# NanoRemotev2.net
KiCad netlist of a schematic drawn in EAGLE
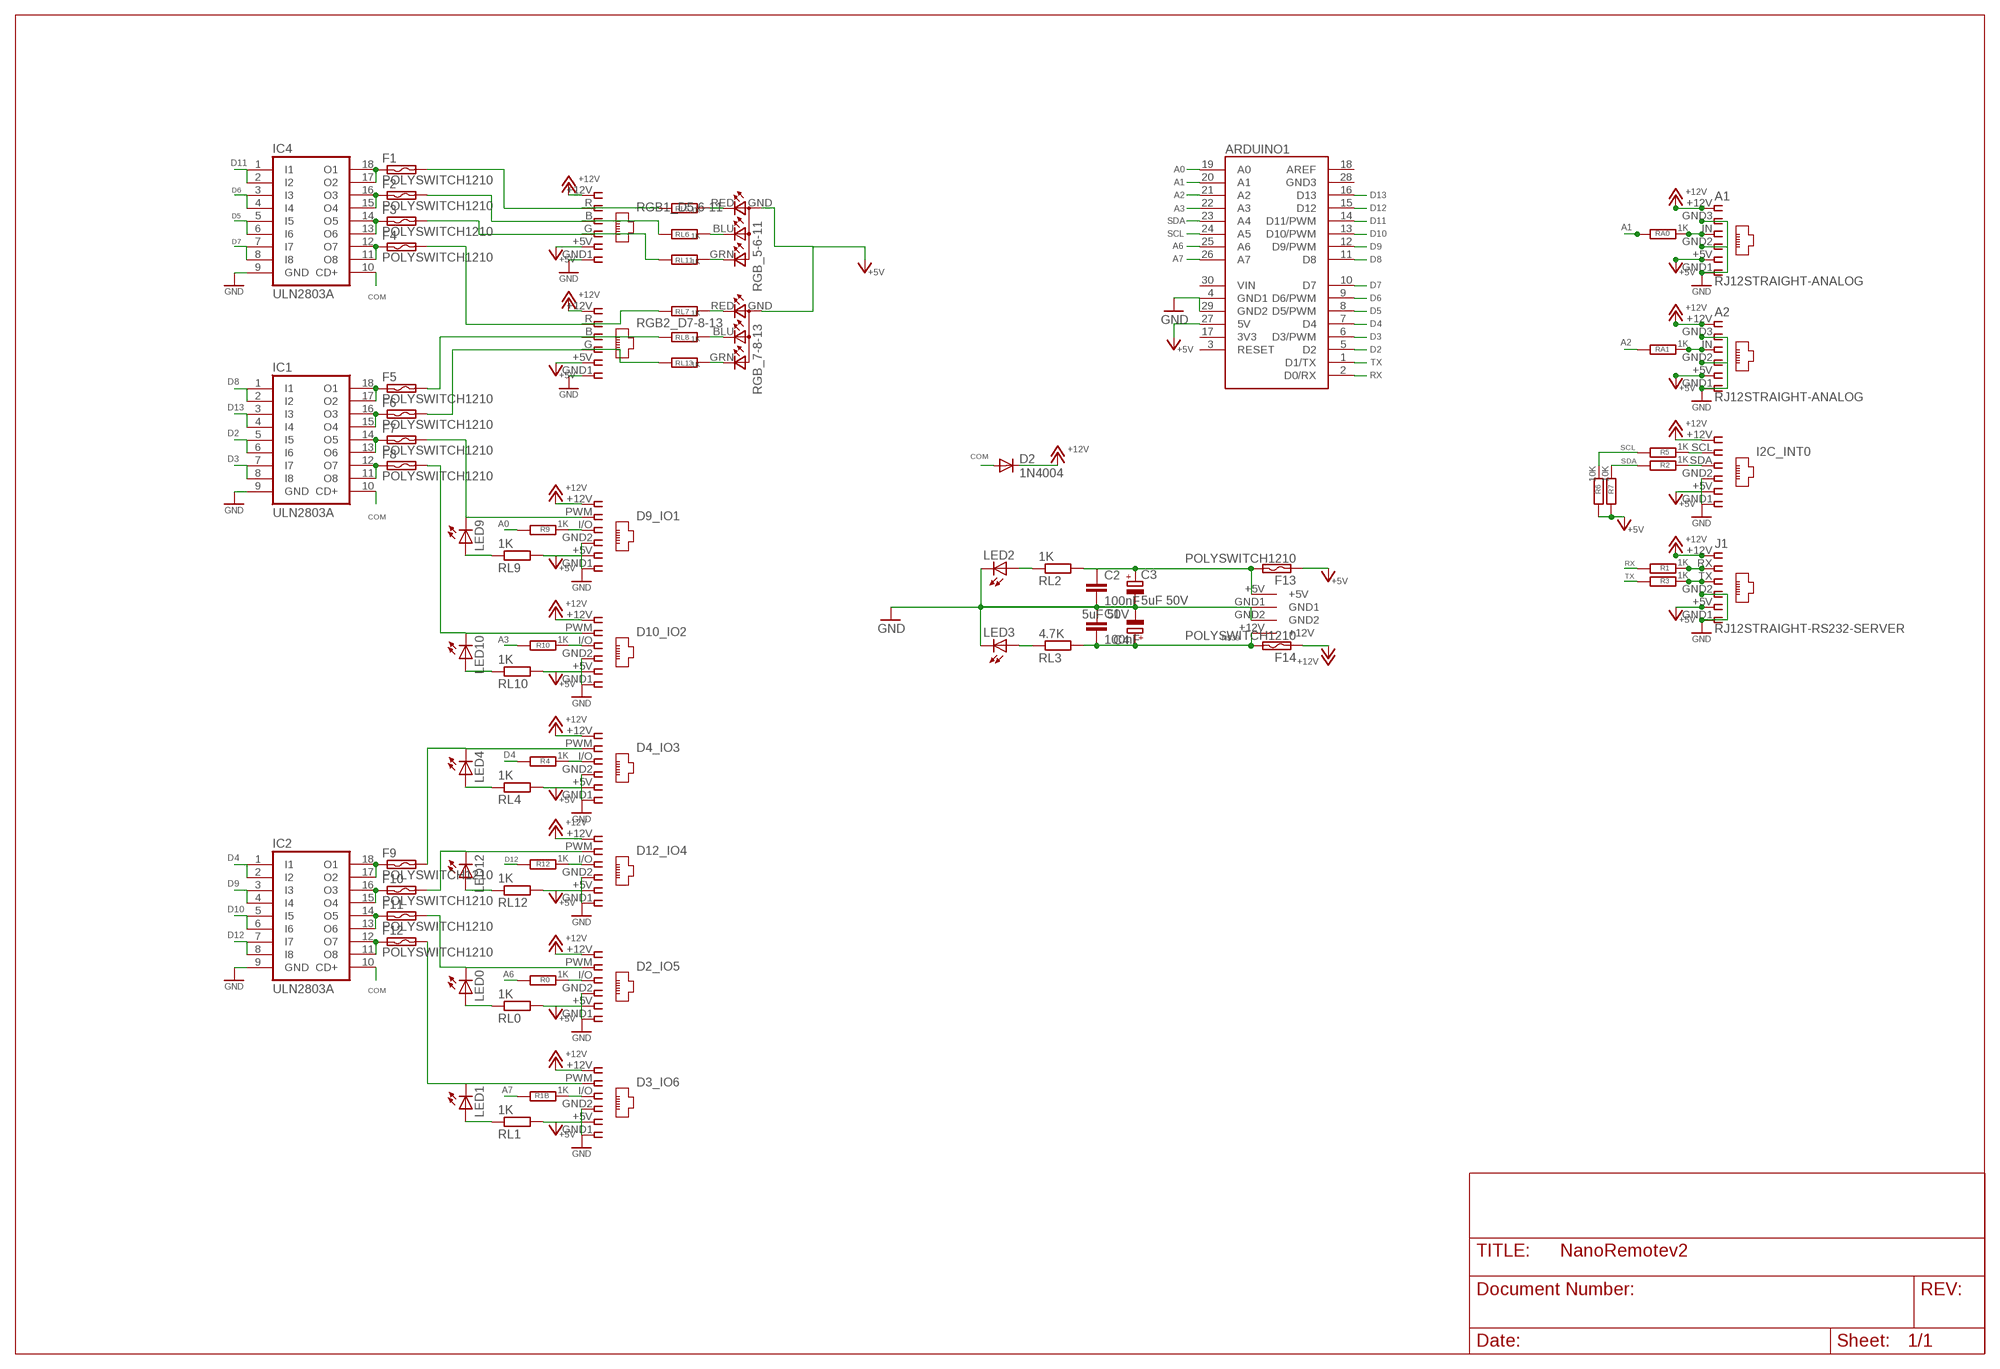
[diagram p0: schematic, sheet 1]

(export (version "E")
  (design (tool "Eeschema 10.0.6"))
  (components
    (comp (ref "A1")
      (value "RJ12STRAIGHT-ANALOG")
      (footprint "eagle-import:RJ12-STRAIGHT-ANALOG")
      (libsource (lib "eagle-import") (part "RJ12STRAIGHT-ANALOG"))
    )
    (comp (ref "A2")
      (value "RJ12STRAIGHT-ANALOG")
      (footprint "eagle-import:RJ12-STRAIGHT-ANALOG")
      (libsource (lib "eagle-import") (part "RJ12STRAIGHT-ANALOG"))
    )
    (comp (ref "ARDUINO1")
      (value "ARDUINO_NANO")
      (footprint "eagle-import:ARDUINO_NANO")
      (libsource (lib "eagle-import") (part "ARDUINO_NANO"))
    )
    (comp (ref "C1")
      (value "100nF")
      (footprint "eagle-import:C1206")
      (libsource (lib "eagle-import") (part "C-EUC1206"))
    )
    (comp (ref "C2")
      (value "100nF")
      (footprint "eagle-import:C1206")
      (libsource (lib "eagle-import") (part "C-EUC1206"))
    )
    (comp (ref "C3")
      (value "5uF 50V")
      (footprint "eagle-import:E3,5-8")
      (libsource (lib "eagle-import") (part "CPOL-EUE3.5-8"))
    )
    (comp (ref "C4")
      (value "5uF 50V")
      (footprint "eagle-import:E3,5-8")
      (libsource (lib "eagle-import") (part "CPOL-EUE3.5-8"))
    )
    (comp (ref "D2")
      (value "1N4004")
      (footprint "eagle-import:DO41-10")
      (libsource (lib "eagle-import") (part "1N4004"))
    )
    (comp (ref "D2_IO5")
      (value "IO5")
      (footprint "eagle-import:RJ12-STRAIGHT")
      (libsource (lib "eagle-import") (part "RJ12STRAIGHT"))
    )
    (comp (ref "D3_IO6")
      (value "IO6")
      (footprint "eagle-import:RJ12-STRAIGHT")
      (libsource (lib "eagle-import") (part "RJ12STRAIGHT"))
    )
    (comp (ref "D4_IO3")
      (value "IO3")
      (footprint "eagle-import:RJ12-STRAIGHT")
      (libsource (lib "eagle-import") (part "RJ12STRAIGHT"))
    )
    (comp (ref "D9_IO1")
      (value "IO1")
      (footprint "eagle-import:RJ12-STRAIGHT")
      (libsource (lib "eagle-import") (part "RJ12STRAIGHT"))
    )
    (comp (ref "D10_IO2")
      (value "IO2")
      (footprint "eagle-import:RJ12-STRAIGHT")
      (libsource (lib "eagle-import") (part "RJ12STRAIGHT"))
    )
    (comp (ref "D12_IO4")
      (value "IO4")
      (footprint "eagle-import:RJ12-STRAIGHT")
      (libsource (lib "eagle-import") (part "RJ12STRAIGHT"))
    )
    (comp (ref "F1")
      (value "POLYSWITCH1210")
      (footprint "eagle-import:C1210")
      (libsource (lib "eagle-import") (part "POLYSWITCH1210"))
    )
    (comp (ref "F2")
      (value "POLYSWITCH1210")
      (footprint "eagle-import:C1210")
      (libsource (lib "eagle-import") (part "POLYSWITCH1210"))
    )
    (comp (ref "F3")
      (value "POLYSWITCH1210")
      (footprint "eagle-import:C1210")
      (libsource (lib "eagle-import") (part "POLYSWITCH1210"))
    )
    (comp (ref "F4")
      (value "POLYSWITCH1210")
      (footprint "eagle-import:C1210")
      (libsource (lib "eagle-import") (part "POLYSWITCH1210"))
    )
    (comp (ref "F5")
      (value "POLYSWITCH1210")
      (footprint "eagle-import:C1210")
      (libsource (lib "eagle-import") (part "POLYSWITCH1210"))
    )
    (comp (ref "F6")
      (value "POLYSWITCH1210")
      (footprint "eagle-import:C1210")
      (libsource (lib "eagle-import") (part "POLYSWITCH1210"))
    )
    (comp (ref "F7")
      (value "POLYSWITCH1210")
      (footprint "eagle-import:C1210")
      (libsource (lib "eagle-import") (part "POLYSWITCH1210"))
    )
    (comp (ref "F8")
      (value "POLYSWITCH1210")
      (footprint "eagle-import:C1210")
      (libsource (lib "eagle-import") (part "POLYSWITCH1210"))
    )
    (comp (ref "F9")
      (value "POLYSWITCH1210")
      (footprint "eagle-import:C1210")
      (libsource (lib "eagle-import") (part "POLYSWITCH1210"))
    )
    (comp (ref "F10")
      (value "POLYSWITCH1210")
      (footprint "eagle-import:C1210")
      (libsource (lib "eagle-import") (part "POLYSWITCH1210"))
    )
    (comp (ref "F11")
      (value "POLYSWITCH1210")
      (footprint "eagle-import:C1210")
      (libsource (lib "eagle-import") (part "POLYSWITCH1210"))
    )
    (comp (ref "F12")
      (value "POLYSWITCH1210")
      (footprint "eagle-import:C1210")
      (libsource (lib "eagle-import") (part "POLYSWITCH1210"))
    )
    (comp (ref "F13")
      (value "POLYSWITCH1210")
      (footprint "eagle-import:C1210")
      (libsource (lib "eagle-import") (part "POLYSWITCH1210"))
    )
    (comp (ref "F14")
      (value "POLYSWITCH1210")
      (footprint "eagle-import:C1210")
      (libsource (lib "eagle-import") (part "POLYSWITCH1210"))
    )
    (comp (ref "I2C_INT0")
      (value "I2C")
      (footprint "eagle-import:RJ12-STRAIGHT-I2C")
      (libsource (lib "eagle-import") (part "RJ12STRAIGHT-I2C"))
    )
    (comp (ref "IC1")
      (value "ULN2803A")
      (footprint "eagle-import:SO18W")
      (libsource (lib "eagle-import") (part "ULN2803A"))
    )
    (comp (ref "IC2")
      (value "ULN2803A")
      (footprint "eagle-import:SO18W")
      (libsource (lib "eagle-import") (part "ULN2803A"))
    )
    (comp (ref "IC4")
      (value "ULN2803A")
      (footprint "eagle-import:SO18W")
      (libsource (lib "eagle-import") (part "ULN2803A"))
    )
    (comp (ref "J1")
      (value "RJ12STRAIGHT-RS232-SERVER")
      (footprint "eagle-import:RJ12-STRAIGHT-RS232")
      (libsource (lib "eagle-import") (part "RJ12STRAIGHT-RS232-SERVER"))
    )
    (comp (ref "LED0")
      (value "LED3MM")
      (footprint "eagle-import:LED3MM")
      (libsource (lib "eagle-import") (part "LED3MM"))
    )
    (comp (ref "LED1")
      (value "LED3MM")
      (footprint "eagle-import:LED3MM")
      (libsource (lib "eagle-import") (part "LED3MM"))
    )
    (comp (ref "LED2")
      (value "LED3MM")
      (footprint "eagle-import:LED3MM")
      (libsource (lib "eagle-import") (part "LED3MM"))
    )
    (comp (ref "LED3")
      (value "LED3MM")
      (footprint "eagle-import:LED3MM")
      (libsource (lib "eagle-import") (part "LED3MM"))
    )
    (comp (ref "LED4")
      (value "LED3MM")
      (footprint "eagle-import:LED3MM")
      (libsource (lib "eagle-import") (part "LED3MM"))
    )
    (comp (ref "LED9")
      (value "LED3MM")
      (footprint "eagle-import:LED3MM")
      (libsource (lib "eagle-import") (part "LED3MM"))
    )
    (comp (ref "LED10")
      (value "LED3MM")
      (footprint "eagle-import:LED3MM")
      (libsource (lib "eagle-import") (part "LED3MM"))
    )
    (comp (ref "LED12")
      (value "LED3MM")
      (footprint "eagle-import:LED3MM")
      (libsource (lib "eagle-import") (part "LED3MM"))
    )
    (comp (ref "R0")
      (value "1K")
      (footprint "eagle-import:M1206")
      (libsource (lib "eagle-import") (part "R-EU_M1206"))
    )
    (comp (ref "R1")
      (value "1K")
      (footprint "eagle-import:M1206")
      (libsource (lib "eagle-import") (part "R-EU_M1206"))
    )
    (comp (ref "R1B")
      (value "1K")
      (footprint "eagle-import:M1206")
      (libsource (lib "eagle-import") (part "R-EU_M1206"))
    )
    (comp (ref "R2")
      (value "1K")
      (footprint "eagle-import:M1206")
      (libsource (lib "eagle-import") (part "R-EU_M1206"))
    )
    (comp (ref "R3")
      (value "1K")
      (footprint "eagle-import:M1206")
      (libsource (lib "eagle-import") (part "R-EU_M1206"))
    )
    (comp (ref "R4")
      (value "1K")
      (footprint "eagle-import:M1206")
      (libsource (lib "eagle-import") (part "R-EU_M1206"))
    )
    (comp (ref "R5")
      (value "1K")
      (footprint "eagle-import:M1206")
      (libsource (lib "eagle-import") (part "R-EU_M1206"))
    )
    (comp (ref "R6")
      (value "10K")
      (footprint "eagle-import:M1206")
      (libsource (lib "eagle-import") (part "R-EU_M1206"))
    )
    (comp (ref "R7")
      (value "10K")
      (footprint "eagle-import:M1206")
      (libsource (lib "eagle-import") (part "R-EU_M1206"))
    )
    (comp (ref "R9")
      (value "1K")
      (footprint "eagle-import:M1206")
      (libsource (lib "eagle-import") (part "R-EU_M1206"))
    )
    (comp (ref "R10")
      (value "1K")
      (footprint "eagle-import:M1206")
      (libsource (lib "eagle-import") (part "R-EU_M1206"))
    )
    (comp (ref "R12")
      (value "1K")
      (footprint "eagle-import:M1206")
      (libsource (lib "eagle-import") (part "R-EU_M1206"))
    )
    (comp (ref "RA0")
      (value "1K")
      (footprint "eagle-import:M1206")
      (libsource (lib "eagle-import") (part "R-EU_M1206"))
    )
    (comp (ref "RA1")
      (value "1K")
      (footprint "eagle-import:M1206")
      (libsource (lib "eagle-import") (part "R-EU_M1206"))
    )
    (comp (ref "RGB1_D5-6-11")
      (value "RGB1")
      (footprint "eagle-import:RJ12-STRAIGHT-RGB")
      (libsource (lib "eagle-import") (part "RJ12STRAIGHT-RGB"))
    )
    (comp (ref "RGB2_D7-8-13")
      (value "RGB2")
      (footprint "eagle-import:RJ12-STRAIGHT-RGB")
      (libsource (lib "eagle-import") (part "RJ12STRAIGHT-RGB"))
    )
    (comp (ref "RGB_5-6-11")
      (value "TOPLED-3")
      (footprint "eagle-import:LED-TRICOLOR-THROUGHHOLE")
      (libsource (lib "eagle-import") (part "TOPLED-3"))
    )
    (comp (ref "RGB_7-8-13")
      (value "TOPLED-3")
      (footprint "eagle-import:LED-TRICOLOR-THROUGHHOLE")
      (libsource (lib "eagle-import") (part "TOPLED-3"))
    )
    (comp (ref "RL0")
      (value "1K")
      (footprint "eagle-import:M1206")
      (libsource (lib "eagle-import") (part "R-EU_M1206"))
    )
    (comp (ref "RL1")
      (value "1K")
      (footprint "eagle-import:M1206")
      (libsource (lib "eagle-import") (part "R-EU_M1206"))
    )
    (comp (ref "RL2")
      (value "1K")
      (footprint "eagle-import:M1206")
      (libsource (lib "eagle-import") (part "R-EU_M1206"))
    )
    (comp (ref "RL3")
      (value "4.7K")
      (footprint "eagle-import:M1206")
      (libsource (lib "eagle-import") (part "R-EU_M1206"))
    )
    (comp (ref "RL4")
      (value "1K")
      (footprint "eagle-import:M1206")
      (libsource (lib "eagle-import") (part "R-EU_M1206"))
    )
    (comp (ref "RL5")
      (value "1K")
      (footprint "eagle-import:M1206")
      (libsource (lib "eagle-import") (part "R-EU_M1206"))
    )
    (comp (ref "RL6")
      (value "1K")
      (footprint "eagle-import:M1206")
      (libsource (lib "eagle-import") (part "R-EU_M1206"))
    )
    (comp (ref "RL7")
      (value "1K")
      (footprint "eagle-import:M1206")
      (libsource (lib "eagle-import") (part "R-EU_M1206"))
    )
    (comp (ref "RL8")
      (value "1K")
      (footprint "eagle-import:M1206")
      (libsource (lib "eagle-import") (part "R-EU_M1206"))
    )
    (comp (ref "RL9")
      (value "1K")
      (footprint "eagle-import:M1206")
      (libsource (lib "eagle-import") (part "R-EU_M1206"))
    )
    (comp (ref "RL10")
      (value "1K")
      (footprint "eagle-import:M1206")
      (libsource (lib "eagle-import") (part "R-EU_M1206"))
    )
    (comp (ref "RL11")
      (value "1K")
      (footprint "eagle-import:M1206")
      (libsource (lib "eagle-import") (part "R-EU_M1206"))
    )
    (comp (ref "RL12")
      (value "1K")
      (footprint "eagle-import:M1206")
      (libsource (lib "eagle-import") (part "R-EU_M1206"))
    )
    (comp (ref "RL13")
      (value "1K")
      (footprint "eagle-import:M1206")
      (libsource (lib "eagle-import") (part "R-EU_M1206"))
    )
    (comp (ref "U$1")
      (value "KPJX-4S-S")
      (footprint "eagle-import:KPJX-4S-S")
      (libsource (lib "eagle-import") (part "KPJX-4S-S"))
    )
  )
  (nets
    (net (code "1") (name "+5V") (class "Default")
      (node (ref "A1") (pin "+5V") (pinfunction "5_+5V") (pintype "power_in"))
      (node (ref "A2") (pin "+5V") (pinfunction "5_+5V") (pintype "power_in"))
      (node (ref "ARDUINO1") (pin "27") (pinfunction "5V_27") (pintype "power_in"))
      (node (ref "D10_IO2") (pin "+5V") (pinfunction "5_+5V") (pintype "power_in"))
      (node (ref "D12_IO4") (pin "+5V") (pinfunction "5_+5V") (pintype "power_in"))
      (node (ref "D2_IO5") (pin "+5V") (pinfunction "5_+5V") (pintype "power_in"))
      (node (ref "D3_IO6") (pin "+5V") (pinfunction "5_+5V") (pintype "power_in"))
      (node (ref "D4_IO3") (pin "+5V") (pinfunction "5_+5V") (pintype "power_in"))
      (node (ref "D9_IO1") (pin "+5V") (pinfunction "5_+5V") (pintype "power_in"))
      (node (ref "F13") (pin "1") (pinfunction "1_1") (pintype "passive"))
      (node (ref "I2C_INT0") (pin "+5V") (pinfunction "5_+5V") (pintype "power_in"))
      (node (ref "J1") (pin "+5V") (pinfunction "5_+5V") (pintype "power_in"))
      (node (ref "R6") (pin "2") (pinfunction "2_2") (pintype "passive"))
      (node (ref "R7") (pin "2") (pinfunction "2_2") (pintype "passive"))
      (node (ref "RGB1_D5-6-11") (pin "+5V") (pinfunction "5_+5V") (pintype "power_in"))
      (node (ref "RGB2_D7-8-13") (pin "+5V") (pinfunction "5_+5V") (pintype "power_in"))
      (node (ref "RGB_5-6-11") (pin "GND") (pinfunction "A2_GND") (pintype "passive"))
      (node (ref "RGB_7-8-13") (pin "GND") (pinfunction "A2_GND") (pintype "passive"))
      (node (ref "RL0") (pin "2") (pinfunction "2_2") (pintype "passive"))
      (node (ref "RL1") (pin "2") (pinfunction "2_2") (pintype "passive"))
      (node (ref "RL10") (pin "2") (pinfunction "2_2") (pintype "passive"))
      (node (ref "RL12") (pin "2") (pinfunction "2_2") (pintype "passive"))
      (node (ref "RL4") (pin "2") (pinfunction "2_2") (pintype "passive"))
      (node (ref "RL9") (pin "2") (pinfunction "2_2") (pintype "passive"))
    )
    (net (code "2") (name "+12V") (class "Default")
      (node (ref "A1") (pin "+12V") (pinfunction "1_+12V") (pintype "power_in"))
      (node (ref "A2") (pin "+12V") (pinfunction "1_+12V") (pintype "power_in"))
      (node (ref "D10_IO2") (pin "+12V") (pinfunction "1_+12V") (pintype "power_in"))
      (node (ref "D12_IO4") (pin "+12V") (pinfunction "1_+12V") (pintype "power_in"))
      (node (ref "D2") (pin "C") (pinfunction "C_C") (pintype "passive"))
      (node (ref "D2_IO5") (pin "+12V") (pinfunction "1_+12V") (pintype "power_in"))
      (node (ref "D3_IO6") (pin "+12V") (pinfunction "1_+12V") (pintype "power_in"))
      (node (ref "D4_IO3") (pin "+12V") (pinfunction "1_+12V") (pintype "power_in"))
      (node (ref "D9_IO1") (pin "+12V") (pinfunction "1_+12V") (pintype "power_in"))
      (node (ref "F14") (pin "1") (pinfunction "1_1") (pintype "passive"))
      (node (ref "I2C_INT0") (pin "+12V") (pinfunction "1_+12V") (pintype "power_in"))
      (node (ref "J1") (pin "+12V") (pinfunction "1_+12V") (pintype "power_in"))
      (node (ref "RGB1_D5-6-11") (pin "+12V") (pinfunction "1_+12V") (pintype "power_in"))
      (node (ref "RGB2_D7-8-13") (pin "+12V") (pinfunction "1_+12V") (pintype "power_in"))
    )
    (net (code "3") (name "/3V3") (class "Default")
      (node (ref "ARDUINO1") (pin "17") (pinfunction "3V3_17") (pintype "power_in"))
    )
    (net (code "4") (name "/A0") (class "Default")
      (node (ref "ARDUINO1") (pin "19") (pinfunction "A0_19") (pintype "bidirectional"))
      (node (ref "R9") (pin "2") (pinfunction "2_2") (pintype "passive"))
    )
    (net (code "5") (name "/A1") (class "Default")
      (node (ref "ARDUINO1") (pin "20") (pinfunction "A1_20") (pintype "bidirectional"))
      (node (ref "RA0") (pin "2") (pinfunction "2_2") (pintype "passive"))
    )
    (net (code "6") (name "/A2") (class "Default")
      (node (ref "ARDUINO1") (pin "21") (pinfunction "A2_21") (pintype "bidirectional"))
      (node (ref "RA1") (pin "2") (pinfunction "2_2") (pintype "passive"))
    )
    (net (code "7") (name "/A3") (class "Default")
      (node (ref "ARDUINO1") (pin "22") (pinfunction "A3_22") (pintype "bidirectional"))
      (node (ref "R10") (pin "2") (pinfunction "2_2") (pintype "passive"))
    )
    (net (code "8") (name "/A6") (class "Default")
      (node (ref "ARDUINO1") (pin "25") (pinfunction "A6_25") (pintype "bidirectional"))
      (node (ref "R0") (pin "2") (pinfunction "2_2") (pintype "passive"))
    )
    (net (code "9") (name "/A7") (class "Default")
      (node (ref "ARDUINO1") (pin "26") (pinfunction "A7_26") (pintype "bidirectional"))
      (node (ref "R1B") (pin "2") (pinfunction "2_2") (pintype "passive"))
    )
    (net (code "10") (name "/COM") (class "Default")
      (node (ref "D2") (pin "A") (pinfunction "A_A") (pintype "passive"))
      (node (ref "IC1") (pin "10") (pinfunction "CD+_10") (pintype "passive"))
      (node (ref "IC2") (pin "10") (pinfunction "CD+_10") (pintype "passive"))
      (node (ref "IC4") (pin "10") (pinfunction "CD+_10") (pintype "passive"))
    )
    (net (code "11") (name "/D2") (class "Default")
      (node (ref "ARDUINO1") (pin "5") (pinfunction "D2_5") (pintype "bidirectional"))
      (node (ref "IC1") (pin "5") (pinfunction "I5_5") (pintype "input"))
      (node (ref "IC1") (pin "6") (pinfunction "I6_6") (pintype "input"))
    )
    (net (code "12") (name "/D3") (class "Default")
      (node (ref "ARDUINO1") (pin "6") (pinfunction "D3/PWM_6") (pintype "bidirectional"))
      (node (ref "IC1") (pin "7") (pinfunction "I7_7") (pintype "input"))
      (node (ref "IC1") (pin "8") (pinfunction "I8_8") (pintype "input"))
    )
    (net (code "13") (name "/D4") (class "Default")
      (node (ref "ARDUINO1") (pin "7") (pinfunction "D4_7") (pintype "bidirectional"))
      (node (ref "IC2") (pin "1") (pinfunction "I1_1") (pintype "input"))
      (node (ref "IC2") (pin "2") (pinfunction "I2_2") (pintype "input"))
      (node (ref "R4") (pin "2") (pinfunction "2_2") (pintype "passive"))
    )
    (net (code "14") (name "/D5") (class "Default")
      (node (ref "ARDUINO1") (pin "8") (pinfunction "D5/PWM_8") (pintype "bidirectional"))
      (node (ref "IC4") (pin "5") (pinfunction "I5_5") (pintype "input"))
      (node (ref "IC4") (pin "6") (pinfunction "I6_6") (pintype "input"))
    )
    (net (code "15") (name "/D6") (class "Default")
      (node (ref "ARDUINO1") (pin "9") (pinfunction "D6/PWM_9") (pintype "bidirectional"))
      (node (ref "IC4") (pin "3") (pinfunction "I3_3") (pintype "input"))
      (node (ref "IC4") (pin "4") (pinfunction "I4_4") (pintype "input"))
    )
    (net (code "16") (name "/D7") (class "Default")
      (node (ref "ARDUINO1") (pin "10") (pinfunction "D7_10") (pintype "bidirectional"))
      (node (ref "IC4") (pin "7") (pinfunction "I7_7") (pintype "input"))
      (node (ref "IC4") (pin "8") (pinfunction "I8_8") (pintype "input"))
    )
    (net (code "17") (name "/D8") (class "Default")
      (node (ref "ARDUINO1") (pin "11") (pinfunction "D8_11") (pintype "bidirectional"))
      (node (ref "IC1") (pin "1") (pinfunction "I1_1") (pintype "input"))
      (node (ref "IC1") (pin "2") (pinfunction "I2_2") (pintype "input"))
    )
    (net (code "18") (name "/D9") (class "Default")
      (node (ref "ARDUINO1") (pin "12") (pinfunction "D9/PWM_12") (pintype "bidirectional"))
      (node (ref "IC2") (pin "3") (pinfunction "I3_3") (pintype "input"))
      (node (ref "IC2") (pin "4") (pinfunction "I4_4") (pintype "input"))
    )
    (net (code "19") (name "/D10") (class "Default")
      (node (ref "ARDUINO1") (pin "13") (pinfunction "D10/PWM_13") (pintype "bidirectional"))
      (node (ref "IC2") (pin "5") (pinfunction "I5_5") (pintype "input"))
      (node (ref "IC2") (pin "6") (pinfunction "I6_6") (pintype "input"))
    )
    (net (code "20") (name "/D11") (class "Default")
      (node (ref "ARDUINO1") (pin "14") (pinfunction "D11/PWM_14") (pintype "bidirectional"))
      (node (ref "IC4") (pin "1") (pinfunction "I1_1") (pintype "input"))
      (node (ref "IC4") (pin "2") (pinfunction "I2_2") (pintype "input"))
    )
    (net (code "21") (name "/D12") (class "Default")
      (node (ref "ARDUINO1") (pin "15") (pinfunction "D12_15") (pintype "bidirectional"))
      (node (ref "IC2") (pin "7") (pinfunction "I7_7") (pintype "input"))
      (node (ref "IC2") (pin "8") (pinfunction "I8_8") (pintype "input"))
      (node (ref "R12") (pin "2") (pinfunction "2_2") (pintype "passive"))
    )
    (net (code "22") (name "/D13") (class "Default")
      (node (ref "ARDUINO1") (pin "16") (pinfunction "D13_16") (pintype "bidirectional"))
      (node (ref "IC1") (pin "3") (pinfunction "I3_3") (pintype "input"))
      (node (ref "IC1") (pin "4") (pinfunction "I4_4") (pintype "input"))
    )
    (net (code "23") (name "/N$39") (class "Default")
      (node (ref "C1") (pin "2") (pinfunction "2_2") (pintype "passive"))
      (node (ref "C4") (pin "+") (pinfunction "+_+") (pintype "passive"))
      (node (ref "F14") (pin "2") (pinfunction "2_2") (pintype "passive"))
      (node (ref "RL3") (pin "2") (pinfunction "2_2") (pintype "passive"))
      (node (ref "U$1") (pin "+12V") (pinfunction "+12V_+12V") (pintype "power_in"))
    )
    (net (code "24") (name "/RX") (class "Default")
      (node (ref "ARDUINO1") (pin "2") (pinfunction "D0/RX_2") (pintype "bidirectional"))
      (node (ref "R1") (pin "2") (pinfunction "2_2") (pintype "passive"))
    )
    (net (code "25") (name "/SCL") (class "Default")
      (node (ref "ARDUINO1") (pin "24") (pinfunction "A5_24") (pintype "bidirectional"))
      (node (ref "R5") (pin "2") (pinfunction "2_2") (pintype "passive"))
      (node (ref "R6") (pin "1") (pinfunction "1_1") (pintype "passive"))
    )
    (net (code "26") (name "/SDA") (class "Default")
      (node (ref "ARDUINO1") (pin "23") (pinfunction "A4_23") (pintype "bidirectional"))
      (node (ref "R2") (pin "2") (pinfunction "2_2") (pintype "passive"))
      (node (ref "R7") (pin "1") (pinfunction "1_1") (pintype "passive"))
    )
    (net (code "27") (name "/TX") (class "Default")
      (node (ref "ARDUINO1") (pin "1") (pinfunction "D1/TX_1") (pintype "bidirectional"))
      (node (ref "R3") (pin "2") (pinfunction "2_2") (pintype "passive"))
    )
    (net (code "28") (name "GND") (class "Default")
      (node (ref "A1") (pin "GND1") (pinfunction "6_GND1") (pintype "power_in"))
      (node (ref "A1") (pin "GND2") (pinfunction "4_GND2") (pintype "power_in"))
      (node (ref "A1") (pin "GND3") (pinfunction "2_GND3") (pintype "bidirectional"))
      (node (ref "A2") (pin "GND1") (pinfunction "6_GND1") (pintype "power_in"))
      (node (ref "A2") (pin "GND2") (pinfunction "4_GND2") (pintype "power_in"))
      (node (ref "A2") (pin "GND3") (pinfunction "2_GND3") (pintype "bidirectional"))
      (node (ref "ARDUINO1") (pin "29") (pinfunction "GND2_29") (pintype "power_in"))
      (node (ref "ARDUINO1") (pin "4") (pinfunction "GND1_4") (pintype "power_in"))
      (node (ref "C1") (pin "1") (pinfunction "1_1") (pintype "passive"))
      (node (ref "C2") (pin "2") (pinfunction "2_2") (pintype "passive"))
      (node (ref "C3") (pin "-") (pinfunction "-_-") (pintype "passive"))
      (node (ref "C4") (pin "-") (pinfunction "-_-") (pintype "passive"))
      (node (ref "D10_IO2") (pin "GND1") (pinfunction "6_GND1") (pintype "power_in"))
      (node (ref "D10_IO2") (pin "GND2") (pinfunction "4_GND2") (pintype "power_in"))
      (node (ref "D12_IO4") (pin "GND1") (pinfunction "6_GND1") (pintype "power_in"))
      (node (ref "D12_IO4") (pin "GND2") (pinfunction "4_GND2") (pintype "power_in"))
      (node (ref "D2_IO5") (pin "GND1") (pinfunction "6_GND1") (pintype "power_in"))
      (node (ref "D2_IO5") (pin "GND2") (pinfunction "4_GND2") (pintype "power_in"))
      (node (ref "D3_IO6") (pin "GND1") (pinfunction "6_GND1") (pintype "power_in"))
      (node (ref "D3_IO6") (pin "GND2") (pinfunction "4_GND2") (pintype "power_in"))
      (node (ref "D4_IO3") (pin "GND1") (pinfunction "6_GND1") (pintype "power_in"))
      (node (ref "D4_IO3") (pin "GND2") (pinfunction "4_GND2") (pintype "power_in"))
      (node (ref "D9_IO1") (pin "GND1") (pinfunction "6_GND1") (pintype "power_in"))
      (node (ref "D9_IO1") (pin "GND2") (pinfunction "4_GND2") (pintype "power_in"))
      (node (ref "I2C_INT0") (pin "GND1") (pinfunction "6_GND1") (pintype "power_in"))
      (node (ref "I2C_INT0") (pin "GND2") (pinfunction "4_GND2") (pintype "power_in"))
      (node (ref "IC1") (pin "9") (pinfunction "GND_9") (pintype "power_in"))
      (node (ref "IC2") (pin "9") (pinfunction "GND_9") (pintype "power_in"))
      (node (ref "IC4") (pin "9") (pinfunction "GND_9") (pintype "power_in"))
      (node (ref "J1") (pin "GND1") (pinfunction "6_GND1") (pintype "power_in"))
      (node (ref "J1") (pin "GND2") (pinfunction "4_GND2") (pintype "power_in"))
      (node (ref "LED2") (pin "K") (pinfunction "C_K") (pintype "passive"))
      (node (ref "LED3") (pin "K") (pinfunction "C_K") (pintype "passive"))
      (node (ref "RGB1_D5-6-11") (pin "GND1") (pinfunction "6_GND1") (pintype "power_in"))
      (node (ref "RGB2_D7-8-13") (pin "GND1") (pinfunction "6_GND1") (pintype "power_in"))
      (node (ref "U$1") (pin "GND1") (pinfunction "GND1_GND1") (pintype "input"))
      (node (ref "U$1") (pin "GND2") (pinfunction "GND2_GND2") (pintype "input"))
    )
    (net (code "29") (name "Net-(A1-3)") (class "Default")
      (node (ref "A1") (pin "IN") (pinfunction "3_IN") (pintype "bidirectional"))
      (node (ref "RA0") (pin "1") (pinfunction "1_1") (pintype "passive"))
    )
    (net (code "30") (name "Net-(A2-3)") (class "Default")
      (node (ref "A2") (pin "IN") (pinfunction "3_IN") (pintype "bidirectional"))
      (node (ref "RA1") (pin "1") (pinfunction "1_1") (pintype "passive"))
    )
    (net (code "31") (name "Net-(C2-Pad1)") (class "Default")
      (node (ref "C2") (pin "1") (pinfunction "1_1") (pintype "passive"))
      (node (ref "C3") (pin "+") (pinfunction "+_+") (pintype "passive"))
      (node (ref "F13") (pin "2") (pinfunction "2_2") (pintype "passive"))
      (node (ref "RL2") (pin "2") (pinfunction "2_2") (pintype "passive"))
      (node (ref "U$1") (pin "+5V") (pinfunction "+5V_+5V") (pintype "power_in"))
    )
    (net (code "32") (name "Net-(D2_IO5-2)") (class "Default")
      (node (ref "D2_IO5") (pin "PWM") (pinfunction "2_PWM") (pintype "bidirectional"))
      (node (ref "F11") (pin "2") (pinfunction "2_2") (pintype "passive"))
      (node (ref "LED0") (pin "K") (pinfunction "C_K") (pintype "passive"))
    )
    (net (code "33") (name "Net-(D2_IO5-3)") (class "Default")
      (node (ref "D2_IO5") (pin "I/O") (pinfunction "3_I/O") (pintype "bidirectional"))
      (node (ref "R0") (pin "1") (pinfunction "1_1") (pintype "passive"))
    )
    (net (code "34") (name "Net-(D3_IO6-2)") (class "Default")
      (node (ref "D3_IO6") (pin "PWM") (pinfunction "2_PWM") (pintype "bidirectional"))
      (node (ref "F12") (pin "2") (pinfunction "2_2") (pintype "passive"))
      (node (ref "LED1") (pin "K") (pinfunction "C_K") (pintype "passive"))
    )
    (net (code "35") (name "Net-(D3_IO6-3)") (class "Default")
      (node (ref "D3_IO6") (pin "I/O") (pinfunction "3_I/O") (pintype "bidirectional"))
      (node (ref "R1B") (pin "1") (pinfunction "1_1") (pintype "passive"))
    )
    (net (code "36") (name "Net-(D4_IO3-2)") (class "Default")
      (node (ref "D4_IO3") (pin "PWM") (pinfunction "2_PWM") (pintype "bidirectional"))
      (node (ref "F9") (pin "2") (pinfunction "2_2") (pintype "passive"))
      (node (ref "LED4") (pin "K") (pinfunction "C_K") (pintype "passive"))
    )
    (net (code "37") (name "Net-(D4_IO3-3)") (class "Default")
      (node (ref "D4_IO3") (pin "I/O") (pinfunction "3_I/O") (pintype "bidirectional"))
      (node (ref "R4") (pin "1") (pinfunction "1_1") (pintype "passive"))
    )
    (net (code "38") (name "Net-(D9_IO1-2)") (class "Default")
      (node (ref "D9_IO1") (pin "PWM") (pinfunction "2_PWM") (pintype "bidirectional"))
      (node (ref "F7") (pin "2") (pinfunction "2_2") (pintype "passive"))
      (node (ref "LED9") (pin "K") (pinfunction "C_K") (pintype "passive"))
    )
    (net (code "39") (name "Net-(D9_IO1-3)") (class "Default")
      (node (ref "D9_IO1") (pin "I/O") (pinfunction "3_I/O") (pintype "bidirectional"))
      (node (ref "R9") (pin "1") (pinfunction "1_1") (pintype "passive"))
    )
    (net (code "40") (name "Net-(D10_IO2-2)") (class "Default")
      (node (ref "D10_IO2") (pin "PWM") (pinfunction "2_PWM") (pintype "bidirectional"))
      (node (ref "F8") (pin "2") (pinfunction "2_2") (pintype "passive"))
      (node (ref "LED10") (pin "K") (pinfunction "C_K") (pintype "passive"))
    )
    (net (code "41") (name "Net-(D10_IO2-3)") (class "Default")
      (node (ref "D10_IO2") (pin "I/O") (pinfunction "3_I/O") (pintype "bidirectional"))
      (node (ref "R10") (pin "1") (pinfunction "1_1") (pintype "passive"))
    )
    (net (code "42") (name "Net-(D12_IO4-2)") (class "Default")
      (node (ref "D12_IO4") (pin "PWM") (pinfunction "2_PWM") (pintype "bidirectional"))
      (node (ref "F10") (pin "2") (pinfunction "2_2") (pintype "passive"))
      (node (ref "LED12") (pin "K") (pinfunction "C_K") (pintype "passive"))
    )
    (net (code "43") (name "Net-(D12_IO4-3)") (class "Default")
      (node (ref "D12_IO4") (pin "I/O") (pinfunction "3_I/O") (pintype "bidirectional"))
      (node (ref "R12") (pin "1") (pinfunction "1_1") (pintype "passive"))
    )
    (net (code "44") (name "Net-(I2C_INT0-2)") (class "Default")
      (node (ref "I2C_INT0") (pin "SCL") (pinfunction "2_SCL") (pintype "bidirectional"))
      (node (ref "R5") (pin "1") (pinfunction "1_1") (pintype "passive"))
    )
    (net (code "45") (name "Net-(I2C_INT0-3)") (class "Default")
      (node (ref "I2C_INT0") (pin "SDA") (pinfunction "3_SDA") (pintype "bidirectional"))
      (node (ref "R2") (pin "1") (pinfunction "1_1") (pintype "passive"))
    )
    (net (code "46") (name "Net-(IC1-O1)") (class "Default")
      (node (ref "F5") (pin "1") (pinfunction "1_1") (pintype "passive"))
      (node (ref "IC1") (pin "17") (pinfunction "O2_17") (pintype "open_collector"))
      (node (ref "IC1") (pin "18") (pinfunction "O1_18") (pintype "open_collector"))
    )
    (net (code "47") (name "Net-(IC1-O3)") (class "Default")
      (node (ref "F6") (pin "1") (pinfunction "1_1") (pintype "passive"))
      (node (ref "IC1") (pin "15") (pinfunction "O4_15") (pintype "open_collector"))
      (node (ref "IC1") (pin "16") (pinfunction "O3_16") (pintype "open_collector"))
    )
    (net (code "48") (name "Net-(IC1-O5)") (class "Default")
      (node (ref "F7") (pin "1") (pinfunction "1_1") (pintype "passive"))
      (node (ref "IC1") (pin "13") (pinfunction "O6_13") (pintype "open_collector"))
      (node (ref "IC1") (pin "14") (pinfunction "O5_14") (pintype "open_collector"))
    )
    (net (code "49") (name "Net-(IC1-O7)") (class "Default")
      (node (ref "F8") (pin "1") (pinfunction "1_1") (pintype "passive"))
      (node (ref "IC1") (pin "11") (pinfunction "O8_11") (pintype "open_collector"))
      (node (ref "IC1") (pin "12") (pinfunction "O7_12") (pintype "open_collector"))
    )
    (net (code "50") (name "Net-(IC2-O1)") (class "Default")
      (node (ref "F9") (pin "1") (pinfunction "1_1") (pintype "passive"))
      (node (ref "IC2") (pin "17") (pinfunction "O2_17") (pintype "open_collector"))
      (node (ref "IC2") (pin "18") (pinfunction "O1_18") (pintype "open_collector"))
    )
    (net (code "51") (name "Net-(IC2-O3)") (class "Default")
      (node (ref "F10") (pin "1") (pinfunction "1_1") (pintype "passive"))
      (node (ref "IC2") (pin "15") (pinfunction "O4_15") (pintype "open_collector"))
      (node (ref "IC2") (pin "16") (pinfunction "O3_16") (pintype "open_collector"))
    )
    (net (code "52") (name "Net-(IC2-O5)") (class "Default")
      (node (ref "F11") (pin "1") (pinfunction "1_1") (pintype "passive"))
      (node (ref "IC2") (pin "13") (pinfunction "O6_13") (pintype "open_collector"))
      (node (ref "IC2") (pin "14") (pinfunction "O5_14") (pintype "open_collector"))
    )
    (net (code "53") (name "Net-(IC2-O7)") (class "Default")
      (node (ref "F12") (pin "1") (pinfunction "1_1") (pintype "passive"))
      (node (ref "IC2") (pin "11") (pinfunction "O8_11") (pintype "open_collector"))
      (node (ref "IC2") (pin "12") (pinfunction "O7_12") (pintype "open_collector"))
    )
    (net (code "54") (name "Net-(IC4-O1)") (class "Default")
      (node (ref "F1") (pin "1") (pinfunction "1_1") (pintype "passive"))
      (node (ref "IC4") (pin "17") (pinfunction "O2_17") (pintype "open_collector"))
      (node (ref "IC4") (pin "18") (pinfunction "O1_18") (pintype "open_collector"))
    )
    (net (code "55") (name "Net-(IC4-O3)") (class "Default")
      (node (ref "F2") (pin "1") (pinfunction "1_1") (pintype "passive"))
      (node (ref "IC4") (pin "15") (pinfunction "O4_15") (pintype "open_collector"))
      (node (ref "IC4") (pin "16") (pinfunction "O3_16") (pintype "open_collector"))
    )
    (net (code "56") (name "Net-(IC4-O5)") (class "Default")
      (node (ref "F3") (pin "1") (pinfunction "1_1") (pintype "passive"))
      (node (ref "IC4") (pin "13") (pinfunction "O6_13") (pintype "open_collector"))
      (node (ref "IC4") (pin "14") (pinfunction "O5_14") (pintype "open_collector"))
    )
    (net (code "57") (name "Net-(IC4-O7)") (class "Default")
      (node (ref "F4") (pin "1") (pinfunction "1_1") (pintype "passive"))
      (node (ref "IC4") (pin "11") (pinfunction "O8_11") (pintype "open_collector"))
      (node (ref "IC4") (pin "12") (pinfunction "O7_12") (pintype "open_collector"))
    )
    (net (code "58") (name "Net-(J1-2)") (class "Default")
      (node (ref "J1") (pin "RX") (pinfunction "2_RX") (pintype "bidirectional"))
      (node (ref "R1") (pin "1") (pinfunction "1_1") (pintype "passive"))
    )
    (net (code "59") (name "Net-(J1-3)") (class "Default")
      (node (ref "J1") (pin "TX") (pinfunction "3_TX") (pintype "bidirectional"))
      (node (ref "R3") (pin "1") (pinfunction "1_1") (pintype "passive"))
    )
    (net (code "60") (name "Net-(LED0-PadA)") (class "Default")
      (node (ref "LED0") (pin "A") (pinfunction "A_A") (pintype "passive"))
      (node (ref "RL0") (pin "1") (pinfunction "1_1") (pintype "passive"))
    )
    (net (code "61") (name "Net-(LED1-PadA)") (class "Default")
      (node (ref "LED1") (pin "A") (pinfunction "A_A") (pintype "passive"))
      (node (ref "RL1") (pin "1") (pinfunction "1_1") (pintype "passive"))
    )
    (net (code "62") (name "Net-(LED2-PadA)") (class "Default")
      (node (ref "LED2") (pin "A") (pinfunction "A_A") (pintype "passive"))
      (node (ref "RL2") (pin "1") (pinfunction "1_1") (pintype "passive"))
    )
    (net (code "63") (name "Net-(LED3-PadA)") (class "Default")
      (node (ref "LED3") (pin "A") (pinfunction "A_A") (pintype "passive"))
      (node (ref "RL3") (pin "1") (pinfunction "1_1") (pintype "passive"))
    )
    (net (code "64") (name "Net-(LED4-PadA)") (class "Default")
      (node (ref "LED4") (pin "A") (pinfunction "A_A") (pintype "passive"))
      (node (ref "RL4") (pin "1") (pinfunction "1_1") (pintype "passive"))
    )
    (net (code "65") (name "Net-(LED9-PadA)") (class "Default")
      (node (ref "LED9") (pin "A") (pinfunction "A_A") (pintype "passive"))
      (node (ref "RL9") (pin "1") (pinfunction "1_1") (pintype "passive"))
    )
    (net (code "66") (name "Net-(LED10-PadA)") (class "Default")
      (node (ref "LED10") (pin "A") (pinfunction "A_A") (pintype "passive"))
      (node (ref "RL10") (pin "1") (pinfunction "1_1") (pintype "passive"))
    )
    (net (code "67") (name "Net-(LED12-PadA)") (class "Default")
      (node (ref "LED12") (pin "A") (pinfunction "A_A") (pintype "passive"))
      (node (ref "RL12") (pin "1") (pinfunction "1_1") (pintype "passive"))
    )
    (net (code "68") (name "Net-(RGB1_D5-6-11-2)") (class "Default")
      (node (ref "F1") (pin "2") (pinfunction "2_2") (pintype "passive"))
      (node (ref "RGB1_D5-6-11") (pin "R") (pinfunction "2_R") (pintype "bidirectional"))
      (node (ref "RL5") (pin "1") (pinfunction "1_1") (pintype "passive"))
    )
    (net (code "69") (name "Net-(RGB1_D5-6-11-3)") (class "Default")
      (node (ref "F2") (pin "2") (pinfunction "2_2") (pintype "passive"))
      (node (ref "RGB1_D5-6-11") (pin "B") (pinfunction "3_B") (pintype "bidirectional"))
      (node (ref "RL6") (pin "1") (pinfunction "1_1") (pintype "passive"))
    )
    (net (code "70") (name "Net-(RGB1_D5-6-11-4)") (class "Default")
      (node (ref "F3") (pin "2") (pinfunction "2_2") (pintype "passive"))
      (node (ref "RGB1_D5-6-11") (pin "G") (pinfunction "4_G") (pintype "power_in"))
      (node (ref "RL11") (pin "1") (pinfunction "1_1") (pintype "passive"))
    )
    (net (code "71") (name "Net-(RGB2_D7-8-13-2)") (class "Default")
      (node (ref "F4") (pin "2") (pinfunction "2_2") (pintype "passive"))
      (node (ref "RGB2_D7-8-13") (pin "R") (pinfunction "2_R") (pintype "bidirectional"))
      (node (ref "RL7") (pin "1") (pinfunction "1_1") (pintype "passive"))
    )
    (net (code "72") (name "Net-(RGB2_D7-8-13-3)") (class "Default")
      (node (ref "F5") (pin "2") (pinfunction "2_2") (pintype "passive"))
      (node (ref "RGB2_D7-8-13") (pin "B") (pinfunction "3_B") (pintype "bidirectional"))
      (node (ref "RL8") (pin "1") (pinfunction "1_1") (pintype "passive"))
    )
    (net (code "73") (name "Net-(RGB2_D7-8-13-4)") (class "Default")
      (node (ref "F6") (pin "2") (pinfunction "2_2") (pintype "passive"))
      (node (ref "RGB2_D7-8-13") (pin "G") (pinfunction "4_G") (pintype "power_in"))
      (node (ref "RL13") (pin "1") (pinfunction "1_1") (pintype "passive"))
    )
    (net (code "74") (name "Net-(RGB_5-6-11-CBLUE)") (class "Default")
      (node (ref "RGB_5-6-11") (pin "BLU") (pinfunction "CBLUE_BLU") (pintype "passive"))
      (node (ref "RL6") (pin "2") (pinfunction "2_2") (pintype "passive"))
    )
    (net (code "75") (name "Net-(RGB_5-6-11-CGREEN)") (class "Default")
      (node (ref "RGB_5-6-11") (pin "GRN") (pinfunction "CGREEN_GRN") (pintype "passive"))
      (node (ref "RL11") (pin "2") (pinfunction "2_2") (pintype "passive"))
    )
    (net (code "76") (name "Net-(RGB_5-6-11-CRED)") (class "Default")
      (node (ref "RGB_5-6-11") (pin "RED") (pinfunction "CRED_RED") (pintype "passive"))
      (node (ref "RL5") (pin "2") (pinfunction "2_2") (pintype "passive"))
    )
    (net (code "77") (name "Net-(RGB_7-8-13-CBLUE)") (class "Default")
      (node (ref "RGB_7-8-13") (pin "BLU") (pinfunction "CBLUE_BLU") (pintype "passive"))
      (node (ref "RL8") (pin "2") (pinfunction "2_2") (pintype "passive"))
    )
    (net (code "78") (name "Net-(RGB_7-8-13-CGREEN)") (class "Default")
      (node (ref "RGB_7-8-13") (pin "GRN") (pinfunction "CGREEN_GRN") (pintype "passive"))
      (node (ref "RL13") (pin "2") (pinfunction "2_2") (pintype "passive"))
    )
    (net (code "79") (name "Net-(RGB_7-8-13-CRED)") (class "Default")
      (node (ref "RGB_7-8-13") (pin "RED") (pinfunction "CRED_RED") (pintype "passive"))
      (node (ref "RL7") (pin "2") (pinfunction "2_2") (pintype "passive"))
    )
    (net (code "80") (name "unconnected-(ARDUINO1-AREF-Pad18)") (class "Default")
      (node (ref "ARDUINO1") (pin "18") (pinfunction "AREF_18") (pintype "bidirectional"))
    )
    (net (code "81") (name "unconnected-(ARDUINO1-GND3-Pad28)") (class "Default")
      (node (ref "ARDUINO1") (pin "28") (pinfunction "GND3_28") (pintype "bidirectional"))
    )
    (net (code "82") (name "unconnected-(ARDUINO1-RESET-Pad3)") (class "Default")
      (node (ref "ARDUINO1") (pin "3") (pinfunction "RESET_3") (pintype "bidirectional"))
    )
    (net (code "83") (name "unconnected-(ARDUINO1-VIN-Pad30)") (class "Default")
      (node (ref "ARDUINO1") (pin "30") (pinfunction "VIN_30") (pintype "bidirectional"))
    )
  )
)
